# Eagle6_6.net
KiCad netlist of a schematic drawn in EAGLE
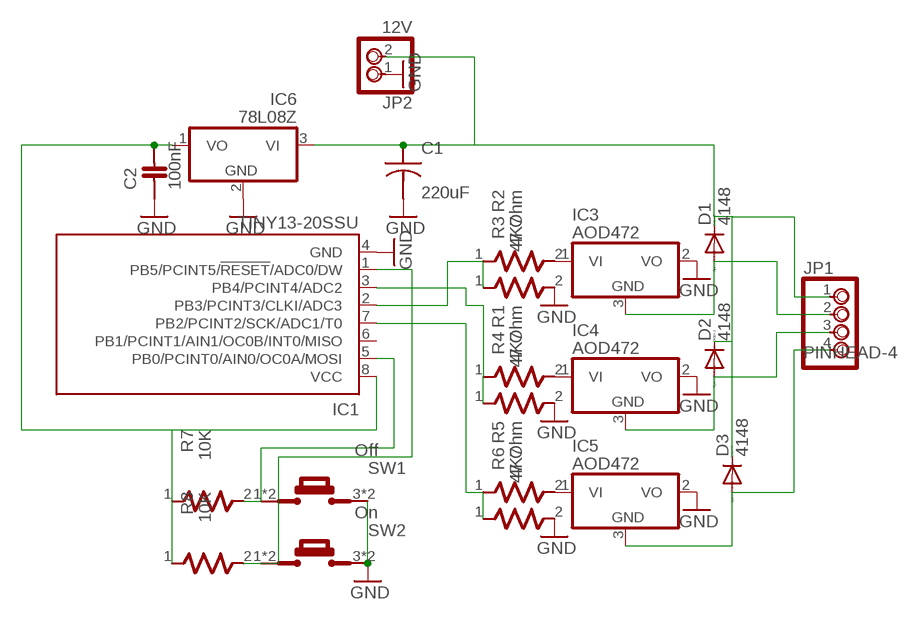
[diagram p0: schematic, sheet 1]

(export (version "E")
  (design (tool "Eeschema 10.0.6"))
  (components
    (comp (ref "C1")
      (value "220uF")
      (footprint "eagle-import:CAP-2,5")
      (libsource (lib "eagle-import") (part "CAP-2,5"))
    )
    (comp (ref "C2")
      (value "100nF")
      (footprint "eagle-import:CAP-NP5")
      (libsource (lib "eagle-import") (part "CAP-NP5"))
    )
    (comp (ref "D1")
      (value "4148")
      (footprint "eagle-import:SMB")
      (libsource (lib "eagle-import") (part "DIODE-SMB"))
    )
    (comp (ref "D2")
      (value "4148")
      (footprint "eagle-import:SMB")
      (libsource (lib "eagle-import") (part "DIODE-SMB"))
    )
    (comp (ref "D3")
      (value "4148")
      (footprint "eagle-import:SMB")
      (libsource (lib "eagle-import") (part "DIODE-SMB"))
    )
    (comp (ref "IC1")
      (value "TINY13-20SSU")
      (footprint "eagle-import:8S1")
      (fields (field (name "MPN") "ATTINY13-20SSU"))
      (libsource (lib "eagle-import") (part "TINY13SSU-20"))
    )
    (comp (ref "IC3")
      (value "AOD472")
      (footprint "eagle-import:TO252")
      (libsource (lib "eagle-import") (part "linear_78DT05"))
    )
    (comp (ref "IC4")
      (value "AOD472")
      (footprint "eagle-import:TO252")
      (libsource (lib "eagle-import") (part "linear_78DT05"))
    )
    (comp (ref "IC5")
      (value "AOD472")
      (footprint "eagle-import:TO252")
      (libsource (lib "eagle-import") (part "linear_78DT05"))
    )
    (comp (ref "IC6")
      (value "78L08Z")
      (footprint "eagle-import:TO92")
      (libsource (lib "eagle-import") (part "78ZL08"))
    )
    (comp (ref "JP1")
      (value "PINHEAD-4")
      (footprint "eagle-import:PINHEAD-4")
      (libsource (lib "eagle-import") (part "PINHEAD-4"))
    )
    (comp (ref "JP2")
      (value "12V")
      (footprint "eagle-import:PINHEAD-2")
      (libsource (lib "eagle-import") (part "PINHEAD-2"))
    )
    (comp (ref "R1")
      (value "47 Ohm")
      (footprint "eagle-import:R-7,5")
      (libsource (lib "eagle-import") (part "R-7,5"))
    )
    (comp (ref "R2")
      (value "47 Ohm")
      (footprint "eagle-import:R-7,5")
      (libsource (lib "eagle-import") (part "R-7,5"))
    )
    (comp (ref "R3")
      (value "4K7")
      (footprint "eagle-import:R-7,5")
      (libsource (lib "eagle-import") (part "R-7,5"))
    )
    (comp (ref "R4")
      (value "4K7")
      (footprint "eagle-import:R-7,5")
      (libsource (lib "eagle-import") (part "R-7,5"))
    )
    (comp (ref "R5")
      (value "47 Ohm")
      (footprint "eagle-import:R-7,5")
      (libsource (lib "eagle-import") (part "R-7,5"))
    )
    (comp (ref "R6")
      (value "4K7")
      (footprint "eagle-import:R-7,5")
      (libsource (lib "eagle-import") (part "R-7,5"))
    )
    (comp (ref "R7")
      (value "10K")
      (footprint "eagle-import:R-7,5")
      (libsource (lib "eagle-import") (part "R-7,5"))
    )
    (comp (ref "R8")
      (value "10K")
      (footprint "eagle-import:R-7,5")
      (libsource (lib "eagle-import") (part "R-7,5"))
    )
    (comp (ref "SW1")
      (value "Off")
      (footprint "eagle-import:KEY-5")
      (libsource (lib "eagle-import") (part "KEY-5"))
    )
    (comp (ref "SW2")
      (value "On")
      (footprint "eagle-import:KEY-5")
      (libsource (lib "eagle-import") (part "KEY-5"))
    )
  )
  (nets
    (net (code "1") (name "GND") (class "Default")
      (node (ref "C1") (pin "-") (pinfunction "2_-") (pintype "passive"))
      (node (ref "C2") (pin "1") (pinfunction "1_1") (pintype "passive"))
      (node (ref "IC1") (pin "4") (pinfunction "GND_4") (pintype "power_in"))
      (node (ref "IC3") (pin "2") (pinfunction "VO_2") (pintype "passive"))
      (node (ref "IC4") (pin "2") (pinfunction "VO_2") (pintype "passive"))
      (node (ref "IC5") (pin "2") (pinfunction "VO_2") (pintype "passive"))
      (node (ref "IC6") (pin "2") (pinfunction "GND_2") (pintype "passive"))
      (node (ref "JP2") (pin "1") (pinfunction "1_1") (pintype "passive"))
      (node (ref "R3") (pin "2") (pinfunction "2_2") (pintype "passive"))
      (node (ref "R4") (pin "2") (pinfunction "2_2") (pintype "passive"))
      (node (ref "R6") (pin "2") (pinfunction "2_2") (pintype "passive"))
      (node (ref "SW1") (pin "3") (pinfunction "2_3") (pintype "bidirectional"))
      (node (ref "SW1") (pin "4") (pinfunction "2_4") (pintype "bidirectional"))
      (node (ref "SW2") (pin "3") (pinfunction "2_3") (pintype "bidirectional"))
      (node (ref "SW2") (pin "4") (pinfunction "2_4") (pintype "bidirectional"))
    )
    (net (code "2") (name "Net-(C1-1)") (class "Default")
      (node (ref "C1") (pin "+") (pinfunction "1_+") (pintype "passive"))
      (node (ref "D1") (pin "C") (pinfunction "C_C") (pintype "passive"))
      (node (ref "D2") (pin "C") (pinfunction "C_C") (pintype "passive"))
      (node (ref "D3") (pin "C") (pinfunction "C_C") (pintype "passive"))
      (node (ref "IC6") (pin "3") (pinfunction "VI_3") (pintype "input"))
      (node (ref "JP1") (pin "1") (pinfunction "1_1") (pintype "passive"))
      (node (ref "JP2") (pin "2") (pinfunction "2_2") (pintype "passive"))
    )
    (net (code "3") (name "Net-(IC1-PB0{slash}PCINT0{slash}AIN0{slash}OC0A{slash}MOSI)") (class "Default")
      (node (ref "IC1") (pin "5") (pinfunction "PB0/PCINT0/AIN0/OC0A/MOSI_5") (pintype "bidirectional"))
      (node (ref "R7") (pin "2") (pinfunction "2_2") (pintype "passive"))
      (node (ref "SW1") (pin "1") (pinfunction "1_1") (pintype "bidirectional"))
      (node (ref "SW1") (pin "2") (pinfunction "1_2") (pintype "bidirectional"))
    )
    (net (code "4") (name "Net-(IC1-PB2{slash}PCINT2{slash}SCK{slash}ADC1{slash}T0)") (class "Default")
      (node (ref "IC1") (pin "7") (pinfunction "PB2/PCINT2/SCK/ADC1/T0_7") (pintype "bidirectional"))
      (node (ref "R5") (pin "1") (pinfunction "1_1") (pintype "passive"))
      (node (ref "R6") (pin "1") (pinfunction "1_1") (pintype "passive"))
    )
    (net (code "5") (name "Net-(IC1-PB3{slash}PCINT3{slash}CLKI{slash}ADC3)") (class "Default")
      (node (ref "IC1") (pin "2") (pinfunction "PB3/PCINT3/CLKI/ADC3_2") (pintype "bidirectional"))
      (node (ref "R2") (pin "1") (pinfunction "1_1") (pintype "passive"))
      (node (ref "R3") (pin "1") (pinfunction "1_1") (pintype "passive"))
    )
    (net (code "6") (name "Net-(IC1-PB4{slash}PCINT4{slash}ADC2)") (class "Default")
      (node (ref "IC1") (pin "3") (pinfunction "PB4/PCINT4/ADC2_3") (pintype "bidirectional"))
      (node (ref "R1") (pin "1") (pinfunction "1_1") (pintype "passive"))
      (node (ref "R4") (pin "1") (pinfunction "1_1") (pintype "passive"))
    )
    (net (code "7") (name "Net-(IC1-PB5{slash}PCINT5{slash}~{RESET}{slash}ADC0{slash}DW)") (class "Default")
      (node (ref "IC1") (pin "1") (pinfunction "PB5/PCINT5/~{RESET}/ADC0/DW_1") (pintype "bidirectional"))
      (node (ref "R8") (pin "2") (pinfunction "2_2") (pintype "passive"))
      (node (ref "SW2") (pin "1") (pinfunction "1_1") (pintype "bidirectional"))
      (node (ref "SW2") (pin "2") (pinfunction "1_2") (pintype "bidirectional"))
    )
    (net (code "8") (name "Net-(IC1-VCC)") (class "Default")
      (node (ref "C2") (pin "2") (pinfunction "2_2") (pintype "passive"))
      (node (ref "IC1") (pin "8") (pinfunction "VCC_8") (pintype "power_in"))
      (node (ref "IC6") (pin "1") (pinfunction "VO_1") (pintype "passive"))
      (node (ref "R7") (pin "1") (pinfunction "1_1") (pintype "passive"))
      (node (ref "R8") (pin "1") (pinfunction "1_1") (pintype "passive"))
    )
    (net (code "9") (name "Net-(IC3-GND)") (class "Default")
      (node (ref "D1") (pin "A") (pinfunction "A_A") (pintype "passive"))
      (node (ref "IC3") (pin "3") (pinfunction "GND_3") (pintype "passive"))
      (node (ref "JP1") (pin "2") (pinfunction "2_2") (pintype "passive"))
    )
    (net (code "10") (name "Net-(IC3-VI)") (class "Default")
      (node (ref "IC3") (pin "1") (pinfunction "VI_1") (pintype "input"))
      (node (ref "R2") (pin "2") (pinfunction "2_2") (pintype "passive"))
    )
    (net (code "11") (name "Net-(IC4-GND)") (class "Default")
      (node (ref "D2") (pin "A") (pinfunction "A_A") (pintype "passive"))
      (node (ref "IC4") (pin "3") (pinfunction "GND_3") (pintype "passive"))
      (node (ref "JP1") (pin "3") (pinfunction "3_3") (pintype "passive"))
    )
    (net (code "12") (name "Net-(IC4-VI)") (class "Default")
      (node (ref "IC4") (pin "1") (pinfunction "VI_1") (pintype "input"))
      (node (ref "R1") (pin "2") (pinfunction "2_2") (pintype "passive"))
    )
    (net (code "13") (name "Net-(IC5-GND)") (class "Default")
      (node (ref "D3") (pin "A") (pinfunction "A_A") (pintype "passive"))
      (node (ref "IC5") (pin "3") (pinfunction "GND_3") (pintype "passive"))
      (node (ref "JP1") (pin "4") (pinfunction "4_4") (pintype "passive"))
    )
    (net (code "14") (name "Net-(IC5-VI)") (class "Default")
      (node (ref "IC5") (pin "1") (pinfunction "VI_1") (pintype "input"))
      (node (ref "R5") (pin "2") (pinfunction "2_2") (pintype "passive"))
    )
    (net (code "15") (name "unconnected-(IC1-PB1{slash}PCINT1{slash}AIN1{slash}OC0B{slash}INT0{slash}MISO-Pad6)") (class "Default")
      (node (ref "IC1") (pin "6") (pinfunction "PB1/PCINT1/AIN1/OC0B/INT0/MISO_6") (pintype "bidirectional"))
    )
  )
)
